# TM_FM_BLEV10.net
KiCad netlist of a schematic drawn in Altium Designer
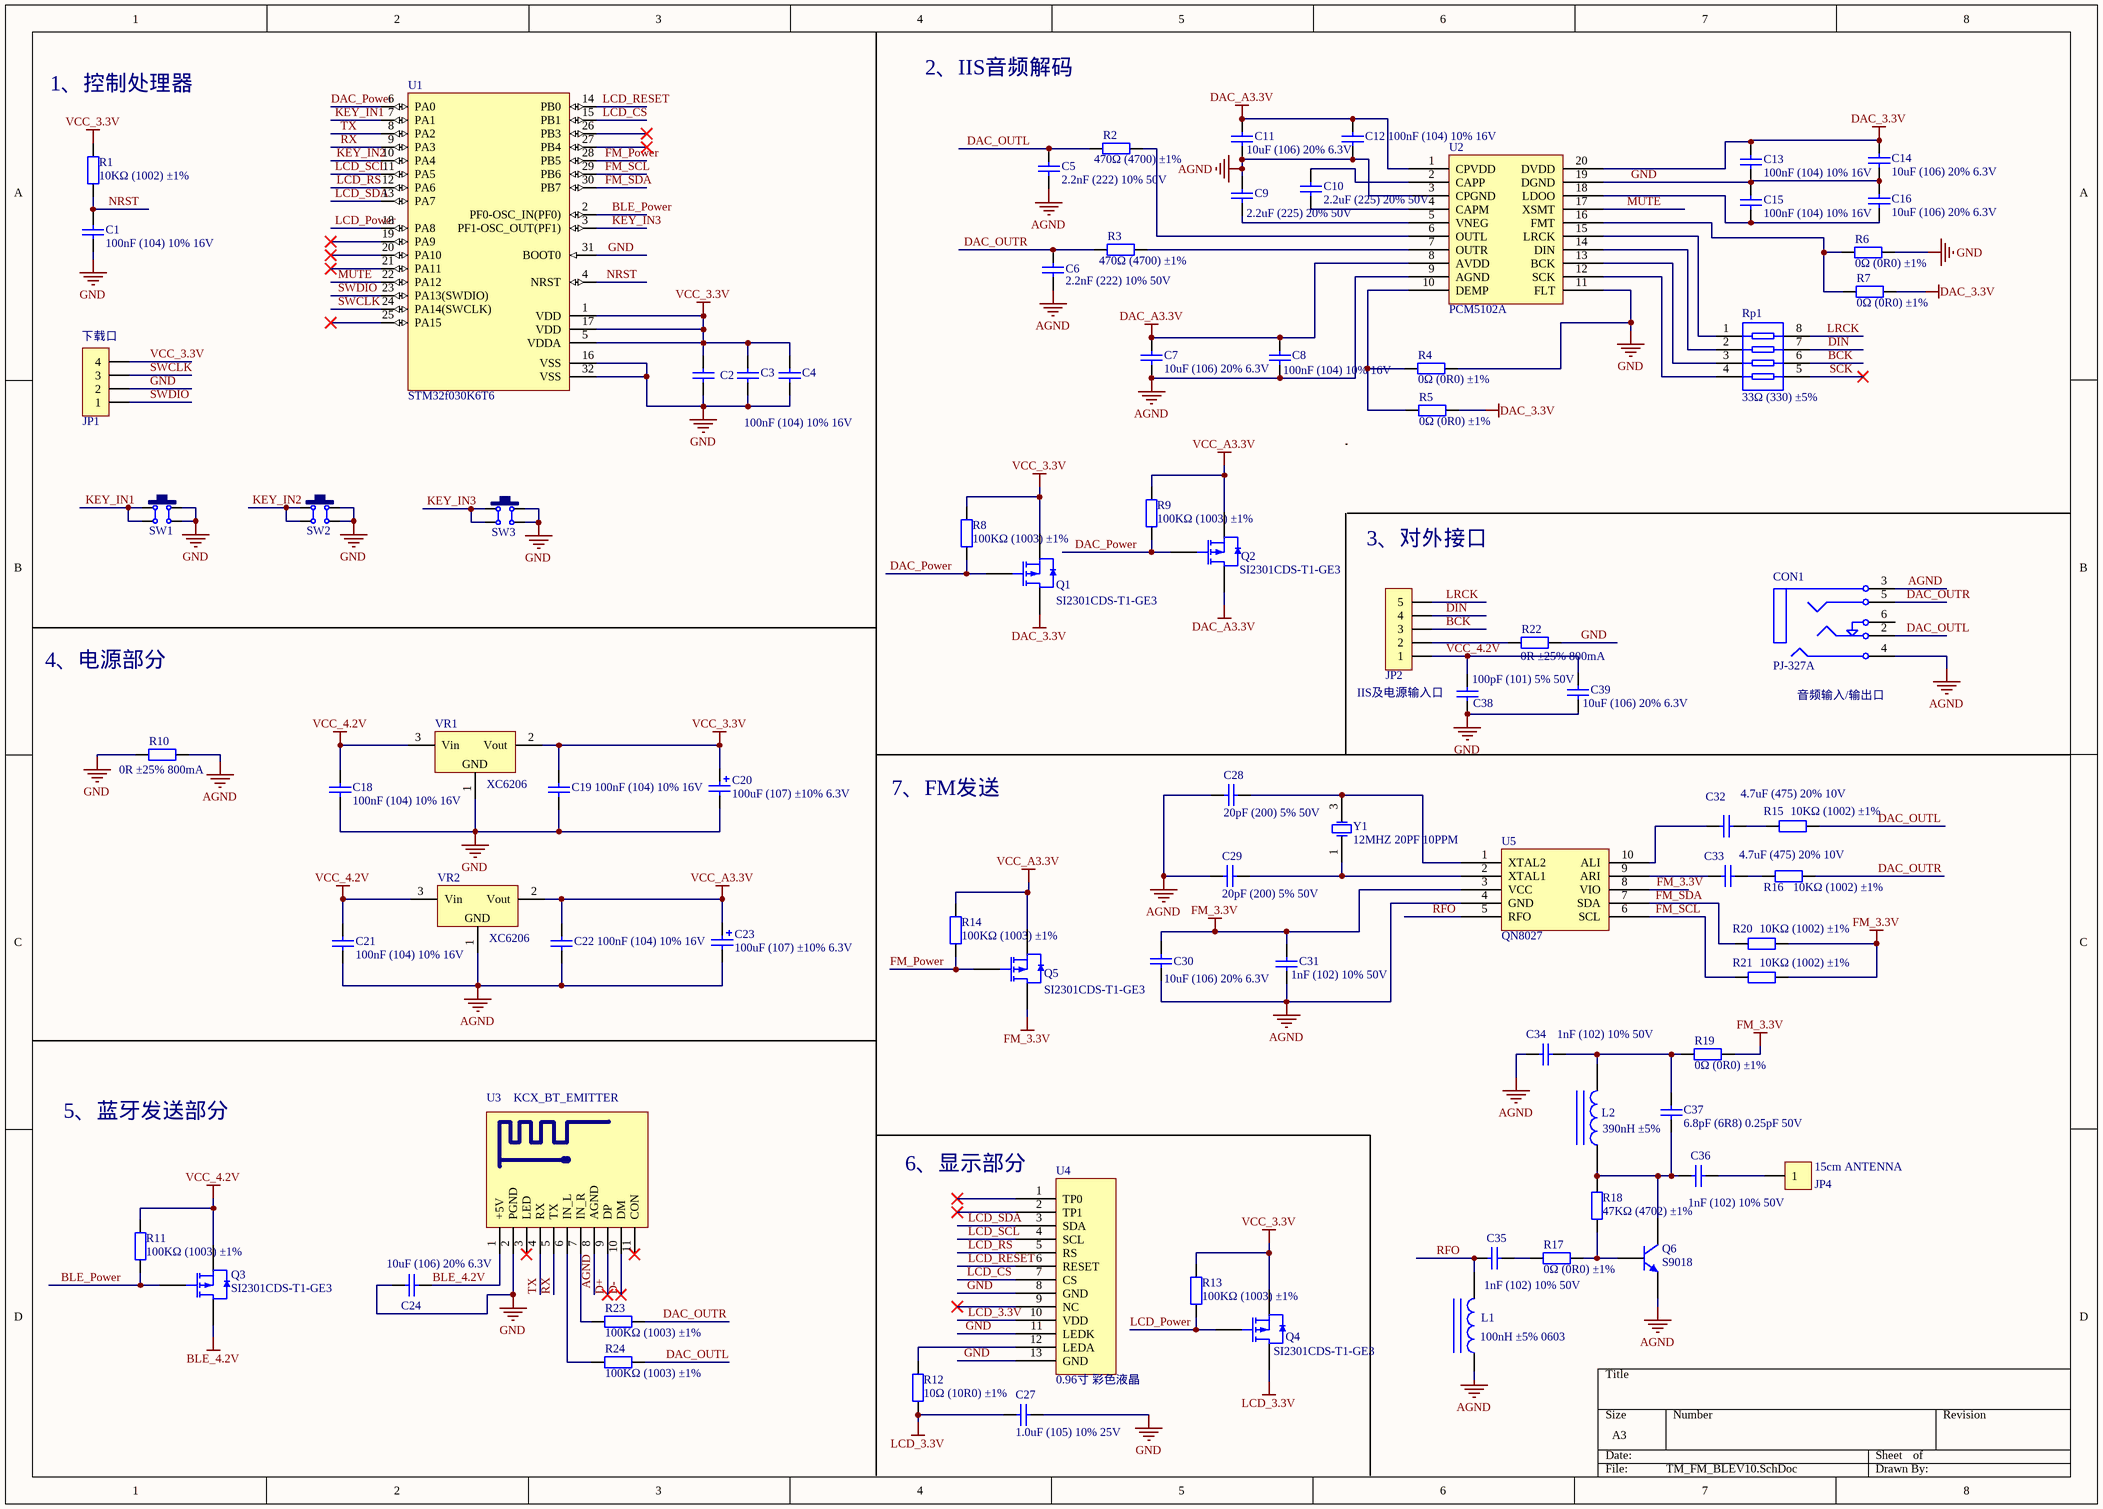
[diagram p0: TM_FM_BLEV10.SchDoc]

(export (version "E")
  (design (tool "Eeschema 10.0.6"))
  (components
    (comp (ref "C1")
      (value "100nF (104) 10% 16V")
      (footprint "0402_C")
      (description "贴片电容")
      (libsource (lib "Cap") (part "0402 100nF (104) 10% 16V"))
    )
    (comp (ref "C2")
      (value "100nF (104) 10% 16V")
      (footprint "0402_C")
      (description "贴片电容")
      (libsource (lib "Cap") (part "0402 100nF (104) 10% 16V"))
    )
    (comp (ref "C3")
      (value "100nF (104) 10% 16V")
      (footprint "0402_C")
      (description "贴片电容")
      (libsource (lib "Cap") (part "0402 100nF (104) 10% 16V"))
    )
    (comp (ref "C4")
      (value "100nF (104) 10% 16V")
      (footprint "0402_C")
      (description "贴片电容")
      (libsource (lib "Cap") (part "0402 100nF (104) 10% 16V"))
    )
    (comp (ref "C5")
      (value "2.2nF (222) 10% 50V")
      (footprint "0402_C")
      (description "贴片电容")
      (libsource (lib "Cap") (part "0402 2.2nF (222) 10% 50V"))
    )
    (comp (ref "C6")
      (value "2.2nF (222) 10% 50V")
      (footprint "0402_C")
      (description "贴片电容")
      (libsource (lib "Cap") (part "0402 2.2nF (222) 10% 50V"))
    )
    (comp (ref "C7")
      (value "10uF (106) 20% 6.3V")
      (footprint "0402_C")
      (description "贴片电容")
      (libsource (lib "Cap") (part "0402 10uF (106) 20% 6.3V"))
    )
    (comp (ref "C8")
      (value "100nF (104) 10% 16V")
      (footprint "0402_C")
      (description "贴片电容")
      (libsource (lib "Cap") (part "0402 100nF (104) 10% 16V"))
    )
    (comp (ref "C9")
      (value "2.2uF (225) 20% 50V")
      (footprint "0402_C")
      (description "贴片电容")
      (libsource (lib "Cap") (part "0402 2.2nF (222) 10% 50V"))
    )
    (comp (ref "C10")
      (value "2.2uF (225) 20% 50V")
      (footprint "0402_C")
      (description "贴片电容")
      (libsource (lib "Cap") (part "0402 2.2nF (222) 10% 50V"))
    )
    (comp (ref "C11")
      (value "10uF (106) 20% 6.3V")
      (footprint "0402_C")
      (description "贴片电容")
      (libsource (lib "Cap") (part "0402 10uF (106) 20% 6.3V"))
    )
    (comp (ref "C12")
      (value "100nF (104) 10% 16V")
      (footprint "0402_C")
      (description "贴片电容")
      (libsource (lib "Cap") (part "0402 100nF (104) 10% 16V"))
    )
    (comp (ref "C13")
      (value "100nF (104) 10% 16V")
      (footprint "0402_C")
      (description "贴片电容")
      (libsource (lib "Cap") (part "0402 100nF (104) 10% 16V"))
    )
    (comp (ref "C14")
      (value "10uF (106) 20% 6.3V")
      (footprint "0402_C")
      (description "贴片电容")
      (libsource (lib "Cap") (part "0402 10uF (106) 20% 6.3V"))
    )
    (comp (ref "C15")
      (value "100nF (104) 10% 16V")
      (footprint "0402_C")
      (description "贴片电容")
      (libsource (lib "Cap") (part "0402 100nF (104) 10% 16V"))
    )
    (comp (ref "C16")
      (value "10uF (106) 20% 6.3V")
      (footprint "0402_C")
      (description "贴片电容")
      (libsource (lib "Cap") (part "0402 10uF (106) 20% 6.3V"))
    )
    (comp (ref "C18")
      (value "100nF (104) 10% 16V")
      (footprint "0402_C")
      (description "贴片电容")
      (libsource (lib "Cap") (part "0402 100nF (104) 10% 16V"))
    )
    (comp (ref "C19")
      (value "100nF (104) 10% 16V")
      (footprint "0402_C")
      (description "贴片电容")
      (libsource (lib "Cap") (part "0402 100nF (104) 10% 16V"))
    )
    (comp (ref "C20")
      (value "100uF (107) ±10% 6.3V")
      (footprint "CASE-B_3528")
      (description "钽电容")
      (libsource (lib "Cap") (part "3528 100uF (107) 10% 6.3V"))
    )
    (comp (ref "C21")
      (value "100nF (104) 10% 16V")
      (footprint "0402_C")
      (description "贴片电容")
      (libsource (lib "Cap") (part "0402 100nF (104) 10% 16V"))
    )
    (comp (ref "C22")
      (value "100nF (104) 10% 16V")
      (footprint "0402_C")
      (description "贴片电容")
      (libsource (lib "Cap") (part "0402 100nF (104) 10% 16V"))
    )
    (comp (ref "C23")
      (value "100uF (107) ±10% 6.3V")
      (footprint "CASE-B_3528")
      (description "钽电容")
      (libsource (lib "Cap") (part "3528 100uF (107) 10% 6.3V"))
    )
    (comp (ref "C24")
      (value "10uF (106) 20% 6.3V")
      (footprint "0402_C")
      (description "贴片电容")
      (libsource (lib "Cap") (part "0402 10uF (106) 20% 6.3V"))
    )
    (comp (ref "C27")
      (value "1.0uF (105) 10% 25V")
      (footprint "0402_C")
      (description "贴片电容")
      (libsource (lib "Cap") (part "0402 1.0uF (105) 10% 25V"))
    )
    (comp (ref "C28")
      (value "20pF (200) 5% 50V")
      (footprint "0402_C")
      (description "贴片电容")
      (libsource (lib "Cap") (part "0402 20pF (200) 5% 50V"))
    )
    (comp (ref "C29")
      (value "20pF (200) 5% 50V")
      (footprint "0402_C")
      (description "贴片电容")
      (libsource (lib "Cap") (part "0402 20pF (200) 5% 50V"))
    )
    (comp (ref "C30")
      (value "10uF (106) 20% 6.3V")
      (footprint "0402_C")
      (description "贴片电容")
      (libsource (lib "Cap") (part "0402 10uF (106) 20% 6.3V"))
    )
    (comp (ref "C31")
      (value "1nF (102) 10% 50V")
      (footprint "0402_C")
      (description "贴片电容")
      (libsource (lib "Cap") (part "0402 1nF (102) 10% 50V"))
    )
    (comp (ref "C32")
      (value "4.7uF (475) 20% 10V")
      (footprint "0402_C")
      (description "贴片电容")
      (libsource (lib "Cap") (part "0402 4.7uF (475) 20% 10V"))
    )
    (comp (ref "C33")
      (value "4.7uF (475) 20% 10V")
      (footprint "0402_C")
      (description "贴片电容")
      (libsource (lib "Cap") (part "0402 4.7uF (475) 20% 10V"))
    )
    (comp (ref "C34")
      (value "1nF (102) 10% 50V")
      (footprint "0603_C")
      (description "贴片电容")
      (libsource (lib "Cap") (part "0603 1nF (102) 10% 50V"))
    )
    (comp (ref "C35")
      (value "1nF (102) 10% 50V")
      (footprint "0603_C")
      (description "贴片电容")
      (libsource (lib "Cap") (part "0603 1nF (102) 10% 50V"))
    )
    (comp (ref "C36")
      (value "1nF (102) 10% 50V")
      (footprint "0603_C")
      (description "贴片电容")
      (libsource (lib "Cap") (part "0603 1nF (102) 10% 50V"))
    )
    (comp (ref "C37")
      (value "6.8pF (6R8) 0.25pF 50V")
      (footprint "0603_C")
      (description "贴片电容")
      (libsource (lib "Cap") (part "0603 6.8pF (6R8) 0.25pF 50V"))
    )
    (comp (ref "C38")
      (value "100pF (101) 5% 50V")
      (footprint "0402_C")
      (description "贴片电容")
      (libsource (lib "Cap") (part "0402 100pF (101) 5% 50V"))
    )
    (comp (ref "C39")
      (value "10uF (106) 20% 6.3V")
      (footprint "0402_C")
      (description "贴片电容")
      (libsource (lib "Cap") (part "0402 10uF (106) 20% 6.3V"))
    )
    (comp (ref "CON1") (value "PJ-327A") (footprint "PJ327A-无固定孔") (libsource (lib "接口类") (part "PJ-327A")))
    (comp (ref "JP1")
      (value "HDR-1X4")
      (footprint "简易下载点")
      (description "4P接插件")
      (fields (field (name "版权归属") "黎明电子style"))
      (libsource (lib "接插件") (part "Header 4"))
    )
    (comp (ref "JP2")
      (value "HDR-1X5")
      (footprint "焊接点")
      (description "5P接插件")
      (fields (field (name "版权归属") "黎明电子style"))
      (libsource (lib "接插件") (part "Header 5"))
    )
    (comp (ref "JP4")
      (value "HDR-1X1")
      (footprint "单个焊接点")
      (description "1P接插件")
      (fields (field (name "版权归属") "黎明电子style"))
      (libsource (lib "接插件") (part "Header 1"))
    )
    (comp (ref "L1")
      (value "100nH ±5% 0603")
      (footprint "0603_L")
      (description "贴片电感")
      (libsource (lib "IUD") (part "0603 68nH 5% 0603"))
    )
    (comp (ref "L2")
      (value "390nH ±5%")
      (footprint "0603_L")
      (description "贴片电感")
      (libsource (lib "IUD") (part "0603 33nH 5%"))
    )
    (comp (ref "Q1")
      (value "SI2301CDS-T1-GE3")
      (footprint "SOT-23(SOT-23-3)")
      (description "MOS(场效应管)")
      (libsource (lib "MOS") (part "SI2301CDS-T1-GE3"))
    )
    (comp (ref "Q2")
      (value "SI2301CDS-T1-GE3")
      (footprint "SOT-23(SOT-23-3)")
      (description "MOS(场效应管)")
      (libsource (lib "MOS") (part "SI2301CDS-T1-GE3"))
    )
    (comp (ref "Q3")
      (value "SI2301CDS-T1-GE3")
      (footprint "SOT-23(SOT-23-3)")
      (description "MOS(场效应管)")
      (libsource (lib "MOS") (part "SI2301CDS-T1-GE3"))
    )
    (comp (ref "Q4")
      (value "SI2301CDS-T1-GE3")
      (footprint "SOT-23(SOT-23-3)")
      (description "MOS(场效应管)")
      (libsource (lib "MOS") (part "SI2301CDS-T1-GE3"))
    )
    (comp (ref "Q5")
      (value "SI2301CDS-T1-GE3")
      (footprint "SOT-23(SOT-23-3)")
      (description "MOS(场效应管)")
      (libsource (lib "MOS") (part "SI2301CDS-T1-GE3"))
    )
    (comp (ref "Q6")
      (value "S9018")
      (footprint "SOT-23(SOT-23-3)")
      (description "三极管")
      (libsource (lib "Transistor_NPN") (part "SOT-23 2SC3356-T1B-A    S/YS档"))
    )
    (comp (ref "R1")
      (value "10KΩ (1002) ±1%")
      (footprint "0402_R")
      (description "贴片电阻")
      (libsource (lib "") (part "0402 10KΩ (1002) 1%_1"))
    )
    (comp (ref "R2")
      (value "470Ω (4700) ±1%")
      (footprint "0402_R")
      (description "贴片电阻")
      (libsource (lib "RES") (part "0402 470Ω (4700) 1%"))
    )
    (comp (ref "R3")
      (value "470Ω (4700) ±1%")
      (footprint "0402_R")
      (description "贴片电阻")
      (libsource (lib "RES") (part "0402 470Ω (4700) 1%"))
    )
    (comp (ref "R4")
      (value "0Ω (0R0) ±1%")
      (footprint "0402_R")
      (description "贴片电阻")
      (libsource (lib "RES") (part "0402 0Ω (0R0) 1%"))
    )
    (comp (ref "R5")
      (value "0Ω (0R0) ±1%")
      (footprint "0402_R")
      (description "贴片电阻")
      (libsource (lib "RES") (part "0402 0Ω (0R0) 1%"))
    )
    (comp (ref "R6")
      (value "0Ω (0R0) ±1%")
      (footprint "0402_R")
      (description "贴片电阻")
      (libsource (lib "RES") (part "0402 0Ω (0R0) 1%"))
    )
    (comp (ref "R7")
      (value "0Ω (0R0) ±1%")
      (footprint "0402_R")
      (description "贴片电阻")
      (libsource (lib "RES") (part "0402 0Ω (0R0) 1%"))
    )
    (comp (ref "R8")
      (value "100KΩ (1003) ±1%")
      (footprint "0402_R")
      (description "贴片电阻")
      (libsource (lib "") (part "0402 100KΩ (1003) 1%_1"))
    )
    (comp (ref "R9")
      (value "100KΩ (1003) ±1%")
      (footprint "0402_R")
      (description "贴片电阻")
      (libsource (lib "") (part "0402 100KΩ (1003) 1%_1"))
    )
    (comp (ref "R10")
      (value "0R ±25% 800mA")
      (footprint "0603_R")
      (description "贴片电阻")
      (libsource (lib "RES") (part "0603 0Ω (0R0) 1%"))
    )
    (comp (ref "R11")
      (value "100KΩ (1003) ±1%")
      (footprint "0402_R")
      (description "贴片电阻")
      (libsource (lib "") (part "0402 100KΩ (1003) 1%_1"))
    )
    (comp (ref "R12")
      (value "10Ω (10R0) ±1%")
      (footprint "0402_R")
      (description "贴片电阻")
      (libsource (lib "RES") (part "0402 10Ω (10R0) 1%"))
    )
    (comp (ref "R13")
      (value "100KΩ (1003) ±1%")
      (footprint "0402_R")
      (description "贴片电阻")
      (libsource (lib "") (part "0402 100KΩ (1003) 1%_1"))
    )
    (comp (ref "R14")
      (value "100KΩ (1003) ±1%")
      (footprint "0402_R")
      (description "贴片电阻")
      (libsource (lib "") (part "0402 100KΩ (1003) 1%_1"))
    )
    (comp (ref "R15")
      (value "10KΩ (1002) ±1%")
      (footprint "0402_R")
      (description "贴片电阻")
      (libsource (lib "RES") (part "0402 10KΩ (1002) 1%"))
    )
    (comp (ref "R16")
      (value "10KΩ (1002) ±1%")
      (footprint "0402_R")
      (description "贴片电阻")
      (libsource (lib "RES") (part "0402 10KΩ (1002) 1%"))
    )
    (comp (ref "R17")
      (value "0Ω (0R0) ±1%")
      (footprint "0402_R")
      (description "贴片电阻")
      (libsource (lib "RES") (part "0402 0Ω (0R0) 1%"))
    )
    (comp (ref "R18")
      (value "47KΩ (4702) ±1%")
      (footprint "0402_R")
      (description "贴片电阻")
      (libsource (lib "RES") (part "0402 47KΩ (4702) 1%"))
    )
    (comp (ref "R19")
      (value "0Ω (0R0) ±1%")
      (footprint "0402_R")
      (description "贴片电阻")
      (libsource (lib "RES") (part "0402 0Ω (0R0) 1%"))
    )
    (comp (ref "R20")
      (value "10KΩ (1002) ±1%")
      (footprint "0402_R")
      (description "贴片电阻")
      (libsource (lib "RES") (part "0402 10KΩ (1002) 1%"))
    )
    (comp (ref "R21")
      (value "10KΩ (1002) ±1%")
      (footprint "0402_R")
      (description "贴片电阻")
      (libsource (lib "RES") (part "0402 10KΩ (1002) 1%"))
    )
    (comp (ref "R22")
      (value "0R ±25% 800mA")
      (footprint "0603_R")
      (description "贴片电阻")
      (libsource (lib "RES") (part "0603 0Ω (0R0) 1%"))
    )
    (comp (ref "R23")
      (value "100KΩ (1003) ±1%")
      (footprint "0402_R")
      (description "贴片电阻")
      (libsource (lib "RES") (part "0402 100KΩ (1003) 1%"))
    )
    (comp (ref "R24")
      (value "100KΩ (1003) ±1%")
      (footprint "0402_R")
      (description "贴片电阻")
      (libsource (lib "RES") (part "0402 100KΩ (1003) 1%"))
    )
    (comp (ref "Rp1")
      (value "33Ω (330) ±5%")
      (footprint "0402_Rx4")
      (description "贴片排阻")
      (libsource (lib "RES") (part "0402*4 33Ω (330) 5%"))
    )
    (comp (ref "SW1")
      (value "6x6x5")
      (footprint "TSW SMD-6*6*4.3")
      (description "贴片6x6轻触开关")
      (fields (field (name "版权归属") "黎明电子style"))
      (libsource (lib "按键-开关") (part "TSW SMD-6x6"))
    )
    (comp (ref "SW2")
      (value "6x6x5")
      (footprint "TSW SMD-6*6*4.3")
      (description "贴片6x6轻触开关")
      (fields (field (name "版权归属") "黎明电子style"))
      (libsource (lib "按键-开关") (part "TSW SMD-6x6"))
    )
    (comp (ref "SW3")
      (value "6x6x5")
      (footprint "TSW SMD-6*6*4.3")
      (description "贴片6x6轻触开关")
      (fields (field (name "版权归属") "黎明电子style"))
      (libsource (lib "按键-开关") (part "TSW SMD-6x6"))
    )
    (comp (ref "U1")
      (value "STM32f030K6T6")
      (footprint "LQFP32 7X7_M")
      (libsource (lib "STM32系列单片机") (part "STM32f030K6T6"))
    )
    (comp (ref "U2")
      (value "PCM5102A")
      (footprint "TSSOP20_N")
      (description "音频解码")
      (libsource (lib "IC芯片") (part "PCM5102A"))
    )
    (comp (ref "U3")
      (value "KCX_BT_EMITTER")
      (footprint "蓝牙音频发送模组")
      (libsource (lib "模块") (part "KCX_BT_EMITTER"))
    )
    (comp (ref "U4")
      (value "0.96寸 彩色液晶")
      (footprint "0.96寸 彩色液晶")
      (libsource (lib "显示器件") (part "0.96寸 彩色液晶"))
    )
    (comp (ref "U5") (value "QN8027") (footprint "MSOP10_N") (libsource (lib "IC芯片") (part "QN8027")))
    (comp (ref "VR1") (value "XC6206") (footprint "SOT23-3M") (libsource (lib "IC芯片") (part "XC6206")))
    (comp (ref "VR2") (value "XC6206") (footprint "SOT23-3M") (libsource (lib "IC芯片") (part "XC6206")))
    (comp (ref "Y1")
      (value "12MHZ 20PF 10PPM")
      (footprint "SMD-3225_4P")
      (description "贴片晶振")
      (libsource (lib "CrystalOscillator") (part "SMD-3225_4P  12MHZ 20PF 10PPM"))
    )
  )
  (nets
    (net (code "1") (name "/BCK") (class "Default")
      (node (ref "JP2") (pin "3") (pinfunction "3_3") (pintype "passive"))
      (node (ref "Rp1") (pin "6") (pinfunction "6_6") (pintype "passive"))
    )
    (net (code "2") (name "/BLE_Power") (class "Default")
      (node (ref "Q3") (pin "1") (pinfunction "G_1") (pintype "passive"))
      (node (ref "R11") (pin "1") (pinfunction "1_1") (pintype "passive"))
      (node (ref "U1") (pin "2") (pinfunction "PF0-OSC_IN(PF0)_2") (pintype "bidirectional"))
    )
    (net (code "3") (name "/D+") (class "Default")
      (node (ref "U3") (pin "9") (pinfunction "DP_9") (pintype "passive+no_connect"))
    )
    (net (code "4") (name "/D-") (class "Default")
      (node (ref "U3") (pin "10") (pinfunction "DM_10") (pintype "passive+no_connect"))
    )
    (net (code "5") (name "/DAC_OUTL") (class "Default")
      (node (ref "C5") (pin "1") (pinfunction "1_1") (pintype "passive"))
      (node (ref "CON1") (pin "2") (pinfunction "2_2") (pintype "passive"))
      (node (ref "R15") (pin "1") (pinfunction "1_1") (pintype "passive"))
      (node (ref "R2") (pin "1") (pinfunction "1_1") (pintype "passive"))
      (node (ref "R24") (pin "1") (pinfunction "1_1") (pintype "passive"))
    )
    (net (code "6") (name "/DAC_OUTR") (class "Default")
      (node (ref "C6") (pin "1") (pinfunction "1_1") (pintype "passive"))
      (node (ref "CON1") (pin "5") (pinfunction "5_5") (pintype "passive"))
      (node (ref "R16") (pin "1") (pinfunction "1_1") (pintype "passive"))
      (node (ref "R23") (pin "1") (pinfunction "1_1") (pintype "passive"))
      (node (ref "R3") (pin "1") (pinfunction "1_1") (pintype "passive"))
    )
    (net (code "7") (name "/DAC_Power") (class "Default")
      (node (ref "Q1") (pin "1") (pinfunction "G_1") (pintype "passive"))
      (node (ref "Q2") (pin "1") (pinfunction "G_1") (pintype "passive"))
      (node (ref "R8") (pin "1") (pinfunction "1_1") (pintype "passive"))
      (node (ref "R9") (pin "1") (pinfunction "1_1") (pintype "passive"))
      (node (ref "U1") (pin "6") (pinfunction "PA0_6") (pintype "bidirectional"))
    )
    (net (code "8") (name "/DIN") (class "Default")
      (node (ref "JP2") (pin "4") (pinfunction "4_4") (pintype "passive"))
      (node (ref "Rp1") (pin "7") (pinfunction "7_7") (pintype "passive"))
    )
    (net (code "9") (name "/FM_Power") (class "Default")
      (node (ref "Q5") (pin "1") (pinfunction "G_1") (pintype "passive"))
      (node (ref "R14") (pin "1") (pinfunction "1_1") (pintype "passive"))
      (node (ref "U1") (pin "28") (pinfunction "PB5_28") (pintype "bidirectional"))
    )
    (net (code "10") (name "/FM_SCL") (class "Default")
      (node (ref "R21") (pin "2") (pinfunction "2_2") (pintype "passive"))
      (node (ref "U1") (pin "29") (pinfunction "PB6_29") (pintype "bidirectional"))
      (node (ref "U5") (pin "6") (pinfunction "SCL_6") (pintype "passive"))
    )
    (net (code "11") (name "/FM_SDA") (class "Default")
      (node (ref "R20") (pin "2") (pinfunction "2_2") (pintype "passive"))
      (node (ref "U1") (pin "30") (pinfunction "PB7_30") (pintype "bidirectional"))
      (node (ref "U5") (pin "7") (pinfunction "SDA_7") (pintype "passive"))
    )
    (net (code "12") (name "/KEY_IN1") (class "Default")
      (node (ref "SW1") (pin "1") (pinfunction "1_1") (pintype "passive"))
      (node (ref "SW1") (pin "4") (pinfunction "4_4") (pintype "passive"))
      (node (ref "U1") (pin "7") (pinfunction "PA1_7") (pintype "bidirectional"))
    )
    (net (code "13") (name "/KEY_IN2") (class "Default")
      (node (ref "SW2") (pin "1") (pinfunction "1_1") (pintype "passive"))
      (node (ref "SW2") (pin "4") (pinfunction "4_4") (pintype "passive"))
      (node (ref "U1") (pin "10") (pinfunction "PA4_10") (pintype "bidirectional"))
    )
    (net (code "14") (name "/KEY_IN3") (class "Default")
      (node (ref "SW3") (pin "1") (pinfunction "1_1") (pintype "passive"))
      (node (ref "SW3") (pin "4") (pinfunction "4_4") (pintype "passive"))
      (node (ref "U1") (pin "3") (pinfunction "PF1-OSC_OUT(PF1)_3") (pintype "bidirectional"))
    )
    (net (code "15") (name "/LCD_CS") (class "Default")
      (node (ref "U1") (pin "15") (pinfunction "PB1_15") (pintype "bidirectional"))
      (node (ref "U4") (pin "7") (pinfunction "CS_7") (pintype "passive"))
    )
    (net (code "16") (name "/LCD_Power") (class "Default")
      (node (ref "Q4") (pin "1") (pinfunction "G_1") (pintype "passive"))
      (node (ref "R13") (pin "1") (pinfunction "1_1") (pintype "passive"))
      (node (ref "U1") (pin "18") (pinfunction "PA8_18") (pintype "bidirectional"))
    )
    (net (code "17") (name "/LCD_RESET") (class "Default")
      (node (ref "U1") (pin "14") (pinfunction "PB0_14") (pintype "bidirectional"))
      (node (ref "U4") (pin "6") (pinfunction "RESET_6") (pintype "passive"))
    )
    (net (code "18") (name "/LCD_RS") (class "Default")
      (node (ref "U1") (pin "12") (pinfunction "PA6_12") (pintype "bidirectional"))
      (node (ref "U4") (pin "5") (pinfunction "RS_5") (pintype "passive"))
    )
    (net (code "19") (name "/LCD_SCL") (class "Default")
      (node (ref "U1") (pin "11") (pinfunction "PA5_11") (pintype "bidirectional"))
      (node (ref "U4") (pin "4") (pinfunction "SCL_4") (pintype "passive"))
    )
    (net (code "20") (name "/LCD_SDA") (class "Default")
      (node (ref "U1") (pin "13") (pinfunction "PA7_13") (pintype "bidirectional"))
      (node (ref "U4") (pin "3") (pinfunction "SDA_3") (pintype "passive"))
    )
    (net (code "21") (name "/LRCK") (class "Default")
      (node (ref "JP2") (pin "5") (pinfunction "5_5") (pintype "passive"))
      (node (ref "Rp1") (pin "8") (pinfunction "8_8") (pintype "passive"))
    )
    (net (code "22") (name "/MUTE") (class "Default")
      (node (ref "U1") (pin "22") (pinfunction "PA12_22") (pintype "bidirectional"))
      (node (ref "U2") (pin "17") (pinfunction "XSMT_17") (pintype "passive"))
    )
    (net (code "23") (name "/NRST") (class "Default")
      (node (ref "C1") (pin "2") (pinfunction "2_2") (pintype "passive"))
      (node (ref "R1") (pin "1") (pinfunction "1_1") (pintype "passive"))
      (node (ref "U1") (pin "4") (pinfunction "NRST_4") (pintype "bidirectional"))
    )
    (net (code "24") (name "/RFO") (class "Default")
      (node (ref "C35") (pin "1") (pinfunction "1_1") (pintype "passive"))
      (node (ref "L1") (pin "2") (pinfunction "2_2") (pintype "passive"))
      (node (ref "U5") (pin "5") (pinfunction "RFO_5") (pintype "passive"))
    )
    (net (code "25") (name "/RX") (class "Default")
      (node (ref "U1") (pin "9") (pinfunction "PA3_9") (pintype "bidirectional"))
      (node (ref "U3") (pin "5") (pinfunction "TX_5") (pintype "passive"))
    )
    (net (code "26") (name "/SCK") (class "Default")
      (node (ref "Rp1") (pin "5") (pinfunction "5_5") (pintype "passive+no_connect"))
    )
    (net (code "27") (name "/SWCLK") (class "Default")
      (node (ref "JP1") (pin "3") (pinfunction "3_3") (pintype "passive"))
      (node (ref "U1") (pin "24") (pinfunction "PA14(SWCLK)_24") (pintype "bidirectional"))
    )
    (net (code "28") (name "/SWDIO") (class "Default")
      (node (ref "JP1") (pin "1") (pinfunction "1_1") (pintype "passive"))
      (node (ref "U1") (pin "23") (pinfunction "PA13(SWDIO)_23") (pintype "bidirectional"))
    )
    (net (code "29") (name "/TX") (class "Default")
      (node (ref "U1") (pin "8") (pinfunction "PA2_8") (pintype "bidirectional"))
      (node (ref "U3") (pin "4") (pinfunction "RX_4") (pintype "passive"))
    )
    (net (code "30") (name "AGND") (class "Default")
      (node (ref "C11") (pin "1") (pinfunction "1_1") (pintype "passive"))
      (node (ref "C12") (pin "1") (pinfunction "1_1") (pintype "passive"))
      (node (ref "C21") (pin "2") (pinfunction "2_2") (pintype "passive"))
      (node (ref "C22") (pin "1") (pinfunction "1_1") (pintype "passive"))
      (node (ref "C23") (pin "2") (pinfunction "2_2") (pintype "passive"))
      (node (ref "C28") (pin "1") (pinfunction "1_1") (pintype "passive"))
      (node (ref "C29") (pin "1") (pinfunction "1_1") (pintype "passive"))
      (node (ref "C30") (pin "1") (pinfunction "1_1") (pintype "passive"))
      (node (ref "C31") (pin "1") (pinfunction "1_1") (pintype "passive"))
      (node (ref "C34") (pin "1") (pinfunction "1_1") (pintype "passive"))
      (node (ref "C5") (pin "2") (pinfunction "2_2") (pintype "passive"))
      (node (ref "C6") (pin "2") (pinfunction "2_2") (pintype "passive"))
      (node (ref "C7") (pin "1") (pinfunction "1_1") (pintype "passive"))
      (node (ref "C8") (pin "1") (pinfunction "1_1") (pintype "passive"))
      (node (ref "C9") (pin "2") (pinfunction "2_2") (pintype "passive"))
      (node (ref "CON1") (pin "3") (pinfunction "3_3") (pintype "passive"))
      (node (ref "CON1") (pin "4") (pinfunction "4_4") (pintype "passive"))
      (node (ref "L1") (pin "1") (pinfunction "1_1") (pintype "passive"))
      (node (ref "Q6") (pin "2") (pinfunction "E_2") (pintype "passive"))
      (node (ref "R10") (pin "2") (pinfunction "2_2") (pintype "passive"))
      (node (ref "U2") (pin "3") (pinfunction "CPGND_3") (pintype "passive"))
      (node (ref "U2") (pin "9") (pinfunction "AGND_9") (pintype "passive"))
      (node (ref "U3") (pin "8") (pinfunction "AGND_8") (pintype "passive"))
      (node (ref "U5") (pin "4") (pinfunction "GND_4") (pintype "passive"))
      (node (ref "VR2") (pin "1") (pinfunction "GND_1") (pintype "passive"))
    )
    (net (code "31") (name "BLE_4.2V") (class "Default")
      (node (ref "C24") (pin "1") (pinfunction "1_1") (pintype "passive"))
      (node (ref "Q3") (pin "3") (pinfunction "D_3") (pintype "passive"))
      (node (ref "U3") (pin "1") (pinfunction "+5V_1") (pintype "passive"))
    )
    (net (code "32") (name "DAC_3.3V") (class "Default")
      (node (ref "C13") (pin "2") (pinfunction "2_2") (pintype "passive"))
      (node (ref "C14") (pin "2") (pinfunction "2_2") (pintype "passive"))
      (node (ref "Q1") (pin "3") (pinfunction "D_3") (pintype "passive"))
      (node (ref "R5") (pin "2") (pinfunction "2_2") (pintype "passive"))
      (node (ref "R7") (pin "2") (pinfunction "2_2") (pintype "passive"))
      (node (ref "U2") (pin "20") (pinfunction "DVDD_20") (pintype "passive"))
    )
    (net (code "33") (name "DAC_A3.3V") (class "Default")
      (node (ref "C11") (pin "2") (pinfunction "2_2") (pintype "passive"))
      (node (ref "C12") (pin "2") (pinfunction "2_2") (pintype "passive"))
      (node (ref "C7") (pin "2") (pinfunction "2_2") (pintype "passive"))
      (node (ref "C8") (pin "2") (pinfunction "2_2") (pintype "passive"))
      (node (ref "Q2") (pin "3") (pinfunction "D_3") (pintype "passive"))
      (node (ref "U2") (pin "1") (pinfunction "CPVDD_1") (pintype "passive"))
      (node (ref "U2") (pin "8") (pinfunction "AVDD_8") (pintype "passive"))
    )
    (net (code "34") (name "FM_3.3V") (class "Default")
      (node (ref "C30") (pin "2") (pinfunction "2_2") (pintype "passive"))
      (node (ref "C31") (pin "2") (pinfunction "2_2") (pintype "passive"))
      (node (ref "Q5") (pin "3") (pinfunction "D_3") (pintype "passive"))
      (node (ref "R19") (pin "2") (pinfunction "2_2") (pintype "passive"))
      (node (ref "R20") (pin "1") (pinfunction "1_1") (pintype "passive"))
      (node (ref "R21") (pin "1") (pinfunction "1_1") (pintype "passive"))
      (node (ref "U5") (pin "3") (pinfunction "VCC_3") (pintype "passive"))
      (node (ref "U5") (pin "8") (pinfunction "VIO_8") (pintype "passive"))
    )
    (net (code "35") (name "GND") (class "Default")
      (node (ref "C1") (pin "1") (pinfunction "1_1") (pintype "passive"))
      (node (ref "C13") (pin "1") (pinfunction "1_1") (pintype "passive"))
      (node (ref "C14") (pin "1") (pinfunction "1_1") (pintype "passive"))
      (node (ref "C15") (pin "2") (pinfunction "2_2") (pintype "passive"))
      (node (ref "C16") (pin "2") (pinfunction "2_2") (pintype "passive"))
      (node (ref "C18") (pin "2") (pinfunction "2_2") (pintype "passive"))
      (node (ref "C19") (pin "1") (pinfunction "1_1") (pintype "passive"))
      (node (ref "C2") (pin "1") (pinfunction "1_1") (pintype "passive"))
      (node (ref "C20") (pin "2") (pinfunction "2_2") (pintype "passive"))
      (node (ref "C24") (pin "2") (pinfunction "2_2") (pintype "passive"))
      (node (ref "C27") (pin "1") (pinfunction "1_1") (pintype "passive"))
      (node (ref "C3") (pin "1") (pinfunction "1_1") (pintype "passive"))
      (node (ref "C38") (pin "1") (pinfunction "1_1") (pintype "passive"))
      (node (ref "C39") (pin "1") (pinfunction "1_1") (pintype "passive"))
      (node (ref "C4") (pin "1") (pinfunction "1_1") (pintype "passive"))
      (node (ref "JP1") (pin "2") (pinfunction "2_2") (pintype "passive"))
      (node (ref "R10") (pin "1") (pinfunction "1_1") (pintype "passive"))
      (node (ref "R22") (pin "2") (pinfunction "2_2") (pintype "passive"))
      (node (ref "R4") (pin "2") (pinfunction "2_2") (pintype "passive"))
      (node (ref "R6") (pin "2") (pinfunction "2_2") (pintype "passive"))
      (node (ref "SW1") (pin "2") (pinfunction "2_2") (pintype "passive"))
      (node (ref "SW1") (pin "3") (pinfunction "3_3") (pintype "passive"))
      (node (ref "SW2") (pin "2") (pinfunction "2_2") (pintype "passive"))
      (node (ref "SW2") (pin "3") (pinfunction "3_3") (pintype "passive"))
      (node (ref "SW3") (pin "2") (pinfunction "2_2") (pintype "passive"))
      (node (ref "SW3") (pin "3") (pinfunction "3_3") (pintype "passive"))
      (node (ref "U1") (pin "16") (pinfunction "VSS_16") (pintype "power_in"))
      (node (ref "U1") (pin "31") (pinfunction "BOOT0_31") (pintype "input"))
      (node (ref "U1") (pin "32") (pinfunction "VSS_32") (pintype "power_in"))
      (node (ref "U2") (pin "11") (pinfunction "FLT_11") (pintype "passive"))
      (node (ref "U2") (pin "19") (pinfunction "DGND_19") (pintype "passive"))
      (node (ref "U3") (pin "2") (pinfunction "PGND_2") (pintype "passive"))
      (node (ref "U4") (pin "11") (pinfunction "LEDK_11") (pintype "passive"))
      (node (ref "U4") (pin "13") (pinfunction "GND_13") (pintype "passive"))
      (node (ref "U4") (pin "8") (pinfunction "GND_8") (pintype "passive"))
      (node (ref "VR1") (pin "1") (pinfunction "GND_1") (pintype "passive"))
    )
    (net (code "36") (name "LCD_3.3V") (class "Default")
      (node (ref "C27") (pin "2") (pinfunction "2_2") (pintype "passive"))
      (node (ref "Q4") (pin "3") (pinfunction "D_3") (pintype "passive"))
      (node (ref "R12") (pin "1") (pinfunction "1_1") (pintype "passive"))
      (node (ref "U4") (pin "10") (pinfunction "VDD_10") (pintype "passive"))
    )
    (net (code "37") (name "Net-(C32-Pad2)") (class "Default")
      (node (ref "C32") (pin "2") (pinfunction "2_2") (pintype "passive"))
      (node (ref "R15") (pin "2") (pinfunction "2_2") (pintype "passive"))
    )
    (net (code "38") (name "Net-(C33-Pad2)") (class "Default")
      (node (ref "C33") (pin "2") (pinfunction "2_2") (pintype "passive"))
      (node (ref "R16") (pin "2") (pinfunction "2_2") (pintype "passive"))
    )
    (net (code "39") (name "Net-(C34-Pad2)") (class "Default")
      (node (ref "C34") (pin "2") (pinfunction "2_2") (pintype "passive"))
      (node (ref "C37") (pin "2") (pinfunction "2_2") (pintype "passive"))
      (node (ref "L2") (pin "2") (pinfunction "2_2") (pintype "passive"))
      (node (ref "R19") (pin "1") (pinfunction "1_1") (pintype "passive"))
    )
    (net (code "40") (name "Net-(C35-Pad2)") (class "Default")
      (node (ref "C35") (pin "2") (pinfunction "2_2") (pintype "passive"))
      (node (ref "R17") (pin "1") (pinfunction "1_1") (pintype "passive"))
    )
    (net (code "41") (name "Net-(C36-Pad2)") (class "Default")
      (node (ref "C36") (pin "2") (pinfunction "2_2") (pintype "passive"))
      (node (ref "JP4") (pin "1") (pinfunction "1_1") (pintype "passive"))
    )
    (net (code "42") (name "Net-(JP2-Pad2)") (class "Default")
      (node (ref "JP2") (pin "2") (pinfunction "2_2") (pintype "passive"))
      (node (ref "R22") (pin "1") (pinfunction "1_1") (pintype "passive"))
    )
    (net (code "43") (name "Net-(Q6-B)") (class "Default")
      (node (ref "Q6") (pin "1") (pinfunction "B_1") (pintype "passive"))
      (node (ref "R17") (pin "2") (pinfunction "2_2") (pintype "passive"))
      (node (ref "R18") (pin "1") (pinfunction "1_1") (pintype "passive"))
    )
    (net (code "44") (name "Net-(Q6-C)") (class "Default")
      (node (ref "C36") (pin "1") (pinfunction "1_1") (pintype "passive"))
      (node (ref "C37") (pin "1") (pinfunction "1_1") (pintype "passive"))
      (node (ref "L2") (pin "1") (pinfunction "1_1") (pintype "passive"))
      (node (ref "Q6") (pin "3") (pinfunction "C_3") (pintype "passive"))
      (node (ref "R18") (pin "2") (pinfunction "2_2") (pintype "passive"))
    )
    (net (code "45") (name "Net-(U2-BCK)") (class "Default")
      (node (ref "Rp1") (pin "3") (pinfunction "3_3") (pintype "passive"))
      (node (ref "U2") (pin "13") (pinfunction "BCK_13") (pintype "passive"))
    )
    (net (code "46") (name "Net-(U2-CAPM)") (class "Default")
      (node (ref "C10") (pin "1") (pinfunction "1_1") (pintype "passive"))
      (node (ref "U2") (pin "4") (pinfunction "CAPM_4") (pintype "passive"))
    )
    (net (code "47") (name "Net-(U2-CAPP)") (class "Default")
      (node (ref "C10") (pin "2") (pinfunction "2_2") (pintype "passive"))
      (node (ref "U2") (pin "2") (pinfunction "CAPP_2") (pintype "passive"))
    )
    (net (code "48") (name "Net-(U2-DEMP)") (class "Default")
      (node (ref "R4") (pin "1") (pinfunction "1_1") (pintype "passive"))
      (node (ref "R5") (pin "1") (pinfunction "1_1") (pintype "passive"))
      (node (ref "U2") (pin "10") (pinfunction "DEMP_10") (pintype "passive"))
    )
    (net (code "49") (name "Net-(U2-DIN)") (class "Default")
      (node (ref "Rp1") (pin "2") (pinfunction "2_2") (pintype "passive"))
      (node (ref "U2") (pin "14") (pinfunction "DIN_14") (pintype "passive"))
    )
    (net (code "50") (name "Net-(U2-FMT)") (class "Default")
      (node (ref "R6") (pin "1") (pinfunction "1_1") (pintype "passive"))
      (node (ref "R7") (pin "1") (pinfunction "1_1") (pintype "passive"))
      (node (ref "U2") (pin "16") (pinfunction "FMT_16") (pintype "passive"))
    )
    (net (code "51") (name "Net-(U2-LDOO)") (class "Default")
      (node (ref "C15") (pin "1") (pinfunction "1_1") (pintype "passive"))
      (node (ref "C16") (pin "1") (pinfunction "1_1") (pintype "passive"))
      (node (ref "U2") (pin "18") (pinfunction "LDOO_18") (pintype "passive"))
    )
    (net (code "52") (name "Net-(U2-LRCK)") (class "Default")
      (node (ref "Rp1") (pin "1") (pinfunction "1_1") (pintype "passive"))
      (node (ref "U2") (pin "15") (pinfunction "LRCK_15") (pintype "passive"))
    )
    (net (code "53") (name "Net-(U2-OUTL)") (class "Default")
      (node (ref "R2") (pin "2") (pinfunction "2_2") (pintype "passive"))
      (node (ref "U2") (pin "6") (pinfunction "OUTL_6") (pintype "passive"))
    )
    (net (code "54") (name "Net-(U2-OUTR)") (class "Default")
      (node (ref "R3") (pin "2") (pinfunction "2_2") (pintype "passive"))
      (node (ref "U2") (pin "7") (pinfunction "OUTR_7") (pintype "passive"))
    )
    (net (code "55") (name "Net-(U2-SCK)") (class "Default")
      (node (ref "Rp1") (pin "4") (pinfunction "4_4") (pintype "passive"))
      (node (ref "U2") (pin "12") (pinfunction "SCK_12") (pintype "passive"))
    )
    (net (code "56") (name "Net-(U2-VNEG)") (class "Default")
      (node (ref "C9") (pin "1") (pinfunction "1_1") (pintype "passive"))
      (node (ref "U2") (pin "5") (pinfunction "VNEG_5") (pintype "passive"))
    )
    (net (code "57") (name "Net-(U3-IN_L)") (class "Default")
      (node (ref "R24") (pin "2") (pinfunction "2_2") (pintype "passive"))
      (node (ref "U3") (pin "6") (pinfunction "IN_L_6") (pintype "passive"))
    )
    (net (code "58") (name "Net-(U3-IN_R)") (class "Default")
      (node (ref "R23") (pin "2") (pinfunction "2_2") (pintype "passive"))
      (node (ref "U3") (pin "7") (pinfunction "IN_R_7") (pintype "passive"))
    )
    (net (code "59") (name "Net-(U4-LEDA)") (class "Default")
      (node (ref "R12") (pin "2") (pinfunction "2_2") (pintype "passive"))
      (node (ref "U4") (pin "12") (pinfunction "LEDA_12") (pintype "passive"))
    )
    (net (code "60") (name "Net-(U5-ALI)") (class "Default")
      (node (ref "C32") (pin "1") (pinfunction "1_1") (pintype "passive"))
      (node (ref "U5") (pin "10") (pinfunction "ALI_10") (pintype "passive"))
    )
    (net (code "61") (name "Net-(U5-ARI)") (class "Default")
      (node (ref "C33") (pin "1") (pinfunction "1_1") (pintype "passive"))
      (node (ref "U5") (pin "9") (pinfunction "ARI_9") (pintype "passive"))
    )
    (net (code "62") (name "Net-(U5-XTAL1)") (class "Default")
      (node (ref "C29") (pin "2") (pinfunction "2_2") (pintype "passive"))
      (node (ref "U5") (pin "2") (pinfunction "XTAL1_2") (pintype "passive"))
      (node (ref "Y1") (pin "1") (pinfunction "OSC1_1") (pintype "passive"))
    )
    (net (code "63") (name "Net-(U5-XTAL2)") (class "Default")
      (node (ref "C28") (pin "2") (pinfunction "2_2") (pintype "passive"))
      (node (ref "U5") (pin "1") (pinfunction "XTAL2_1") (pintype "passive"))
      (node (ref "Y1") (pin "3") (pinfunction "OSC2_3") (pintype "passive"))
    )
    (net (code "64") (name "VCC_3.3V") (class "Default")
      (node (ref "C19") (pin "2") (pinfunction "2_2") (pintype "passive"))
      (node (ref "C2") (pin "2") (pinfunction "2_2") (pintype "passive"))
      (node (ref "C20") (pin "1") (pinfunction "1_1") (pintype "passive"))
      (node (ref "C3") (pin "2") (pinfunction "2_2") (pintype "passive"))
      (node (ref "C4") (pin "2") (pinfunction "2_2") (pintype "passive"))
      (node (ref "JP1") (pin "4") (pinfunction "4_4") (pintype "passive"))
      (node (ref "Q1") (pin "2") (pinfunction "S_2") (pintype "passive"))
      (node (ref "Q4") (pin "2") (pinfunction "S_2") (pintype "passive"))
      (node (ref "R1") (pin "2") (pinfunction "2_2") (pintype "passive"))
      (node (ref "R13") (pin "2") (pinfunction "2_2") (pintype "passive"))
      (node (ref "R8") (pin "2") (pinfunction "2_2") (pintype "passive"))
      (node (ref "U1") (pin "1") (pinfunction "VDD_1") (pintype "power_in"))
      (node (ref "U1") (pin "17") (pinfunction "VDD_17") (pintype "power_in"))
      (node (ref "U1") (pin "5") (pinfunction "VDDA_5") (pintype "power_in"))
      (node (ref "VR1") (pin "2") (pinfunction "Vout_2") (pintype "passive"))
    )
    (net (code "65") (name "VCC_4.2V") (class "Default")
      (node (ref "C18") (pin "1") (pinfunction "1_1") (pintype "passive"))
      (node (ref "C21") (pin "1") (pinfunction "1_1") (pintype "passive"))
      (node (ref "C38") (pin "2") (pinfunction "2_2") (pintype "passive"))
      (node (ref "C39") (pin "2") (pinfunction "2_2") (pintype "passive"))
      (node (ref "JP2") (pin "1") (pinfunction "1_1") (pintype "passive"))
      (node (ref "Q3") (pin "2") (pinfunction "S_2") (pintype "passive"))
      (node (ref "R11") (pin "2") (pinfunction "2_2") (pintype "passive"))
      (node (ref "VR1") (pin "3") (pinfunction "Vin_3") (pintype "passive"))
      (node (ref "VR2") (pin "3") (pinfunction "Vin_3") (pintype "passive"))
    )
    (net (code "66") (name "VCC_A3.3V") (class "Default")
      (node (ref "C22") (pin "2") (pinfunction "2_2") (pintype "passive"))
      (node (ref "C23") (pin "1") (pinfunction "1_1") (pintype "passive"))
      (node (ref "Q2") (pin "2") (pinfunction "S_2") (pintype "passive"))
      (node (ref "Q5") (pin "2") (pinfunction "S_2") (pintype "passive"))
      (node (ref "R14") (pin "2") (pinfunction "2_2") (pintype "passive"))
      (node (ref "R9") (pin "2") (pinfunction "2_2") (pintype "passive"))
      (node (ref "VR2") (pin "2") (pinfunction "Vout_2") (pintype "passive"))
    )
    (net (code "67") (name "unconnected-(CON1-Pad6)") (class "Default")
      (node (ref "CON1") (pin "6") (pinfunction "6_6") (pintype "passive"))
    )
    (net (code "68") (name "unconnected-(U1-PA9-Pad19)") (class "Default")
      (node (ref "U1") (pin "19") (pinfunction "PA9_19") (pintype "bidirectional+no_connect"))
    )
    (net (code "69") (name "unconnected-(U1-PA10-Pad20)") (class "Default")
      (node (ref "U1") (pin "20") (pinfunction "PA10_20") (pintype "bidirectional+no_connect"))
    )
    (net (code "70") (name "unconnected-(U1-PA11-Pad21)") (class "Default")
      (node (ref "U1") (pin "21") (pinfunction "PA11_21") (pintype "bidirectional+no_connect"))
    )
    (net (code "71") (name "unconnected-(U1-PA15-Pad25)") (class "Default")
      (node (ref "U1") (pin "25") (pinfunction "PA15_25") (pintype "bidirectional+no_connect"))
    )
    (net (code "72") (name "unconnected-(U1-PB3-Pad26)") (class "Default")
      (node (ref "U1") (pin "26") (pinfunction "PB3_26") (pintype "bidirectional+no_connect"))
    )
    (net (code "73") (name "unconnected-(U1-PB4-Pad27)") (class "Default")
      (node (ref "U1") (pin "27") (pinfunction "PB4_27") (pintype "bidirectional+no_connect"))
    )
    (net (code "74") (name "unconnected-(U3-CON-Pad11)") (class "Default")
      (node (ref "U3") (pin "11") (pinfunction "CON_11") (pintype "passive+no_connect"))
    )
    (net (code "75") (name "unconnected-(U3-LED-Pad3)") (class "Default")
      (node (ref "U3") (pin "3") (pinfunction "LED_3") (pintype "passive+no_connect"))
    )
    (net (code "76") (name "unconnected-(U4-NC-Pad9)") (class "Default")
      (node (ref "U4") (pin "9") (pinfunction "NC_9") (pintype "passive+no_connect"))
    )
    (net (code "77") (name "unconnected-(U4-TP0-Pad1)") (class "Default")
      (node (ref "U4") (pin "1") (pinfunction "TP0_1") (pintype "passive+no_connect"))
    )
    (net (code "78") (name "unconnected-(U4-TP1-Pad2)") (class "Default")
      (node (ref "U4") (pin "2") (pinfunction "TP1_2") (pintype "passive+no_connect"))
    )
  )
)
